# Power.net
KiCad netlist of a schematic drawn in Altium Designer
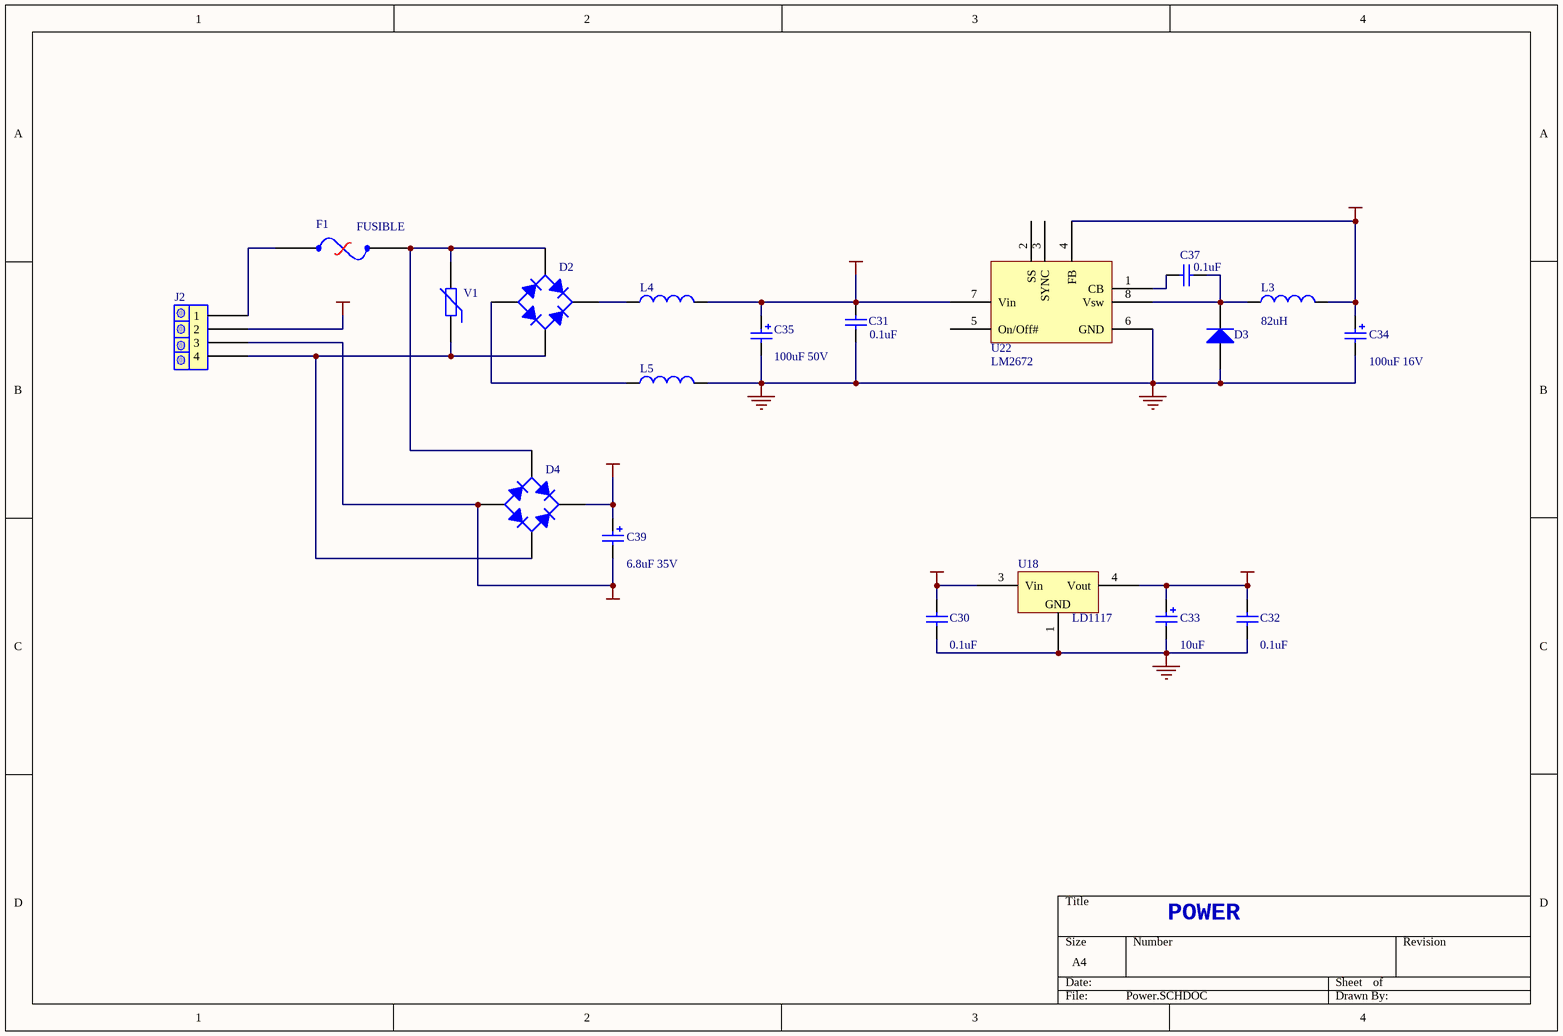
[diagram p0: Power.SCHDOC]

(export (version "E")
  (design (tool "Eeschema 10.0.6"))
  (components
    (comp (ref "C30")
      (value "0.1uF")
      (footprint "_0805")
      (description "Capacitor (Semiconductor SIM Model)")
      (fields (field (name "Comment") "Cap Semi") (field (name "PUBLISHER") "Altium Limited"))
      (libsource (lib "Miscellaneous Devices") (part "Cap Semi"))
    )
    (comp (ref "C31")
      (value "0.1uF")
      (footprint "_0805")
      (description "Capacitor (Semiconductor SIM Model)")
      (fields (field (name "Comment") "Cap Semi") (field (name "PUBLISHER") "Altium Limited"))
      (libsource (lib "Miscellaneous Devices") (part "Cap Semi"))
    )
    (comp (ref "C32")
      (value "0.1uF")
      (footprint "_0805")
      (description "Capacitor (Semiconductor SIM Model)")
      (fields (field (name "Comment") "Cap Semi") (field (name "PUBLISHER") "Altium Limited"))
      (libsource (lib "Miscellaneous Devices") (part "Cap Semi"))
    )
    (comp (ref "C33")
      (value "10uF")
      (footprint "TC3528-1411")
      (description "Polarized Capacitor (Surface Mount)")
      (fields (field (name "Comment") "Cap Pol3") (field (name "PUBLISHER") "Altium Limited"))
      (libsource (lib "Miscellaneous Devices") (part "Cap Pol3"))
    )
    (comp (ref "C34")
      (value "100uF 16V")
      (footprint "TC7360-2924")
      (description "Polarized Capacitor (Surface Mount)")
      (fields (field (name "Comment") "Cap Pol3") (field (name "PUBLISHER") "Altium Limited"))
      (libsource (lib "Miscellaneous Devices") (part "Cap Pol3"))
    )
    (comp (ref "C35")
      (value "100uF 50V")
      (footprint "CAPPR3.5-8X11.5")
      (description "Polarized Capacitor (Radial)")
      (fields (field (name "Comment") "Cap Pol1") (field (name "PUBLISHER") "Altium Limited"))
      (libsource (lib "Miscellaneous Devices") (part "Cap Pol1"))
    )
    (comp (ref "C37")
      (value "0.1uF")
      (footprint "_0805")
      (description "Capacitor (Semiconductor SIM Model)")
      (fields (field (name "Comment") "Cap Semi") (field (name "PUBLISHER") "Altium Limited"))
      (libsource (lib "Miscellaneous Devices") (part "Cap Semi"))
    )
    (comp (ref "C39")
      (value "6.8uF 35V")
      (footprint "TC6032-2412")
      (description "Polarized Capacitor (Surface Mount)")
      (fields (field (name "Comment") "Cap Pol3") (field (name "PUBLISHER") "Altium Limited"))
      (libsource (lib "Miscellaneous Devices") (part "Cap Pol3"))
    )
    (comp (ref "D2")
      (value "Bridge1")
      (footprint "BRIDGE_2A")
      (description "Full Wave Diode Bridge")
      (fields (field (name "PUBLISHER") "Altium Limited"))
      (libsource (lib "Miscellaneous Devices") (part "Bridge1"))
    )
    (comp (ref "D3")
      (value "Diode")
      (footprint "SMA")
      (description "Default Diode")
      (fields (field (name "PUBLISHER") "Altium Limited"))
      (libsource (lib "Miscellaneous Devices") (part "Diode"))
    )
    (comp (ref "D4")
      (value "Bridge1")
      (footprint "BRIDGE_2A")
      (description "Full Wave Diode Bridge")
      (fields (field (name "PUBLISHER") "Altium Limited"))
      (libsource (lib "Miscellaneous Devices") (part "Bridge1"))
    )
    (comp (ref "F1")
      (value "FUSIBLE")
      (footprint "FUSE")
      (description "Resetteable Fuse")
      (libsource (lib "Vending") (part "FUSIBLE"))
    )
    (comp (ref "J2")
      (value "BORNERA_X4")
      (footprint "BORNERA_X4")
      (libsource (lib "Custom") (part "BORNERA_X4"))
    )
    (comp (ref "L3")
      (value "82uH")
      (footprint "POWER_IND")
      (description "Inductor")
      (fields (field (name "PUBLISHER") "Altium Limited"))
      (libsource (lib "Miscellaneous Devices") (part "Inductor"))
    )
    (comp (ref "L4")
      (value "Inductor")
      (footprint "CR3225-1210")
      (fields (field (name "PUBLISHER") "Altium Limited"))
      (libsource (lib "Miscellaneous Devices") (part "Inductor"))
    )
    (comp (ref "L5")
      (value "Inductor")
      (footprint "CR3225-1210")
      (fields (field (name "PUBLISHER") "Altium Limited"))
      (libsource (lib "Miscellaneous Devices") (part "Inductor"))
    )
    (comp (ref "U18")
      (value "LD1117")
      (footprint "SIP-G3/D11.3")
      (description "SMD DPAK Voltage Regulator")
      (libsource (lib "Custom") (part "VREG_3V3_DPAK"))
    )
    (comp (ref "U22")
      (value "LM2672")
      (footprint "SO-G8/D5")
      (description "Simple switcher voltage regulator 1A")
      (libsource (lib "Custom") (part "LM2672"))
    )
    (comp (ref "V1")
      (value "Res Varistor")
      (footprint "CR3216-1206")
      (description "Varistor (Voltage-Sensitive Resistor)")
      (fields (field (name "PUBLISHER") "Altium Limited"))
      (libsource (lib "Miscellaneous Devices") (part "Res Varistor"))
    )
  )
  (nets
    (net (code "1") (name "GND") (class "Default")
      (node (ref "C30") (pin "1") (pinfunction "1_1") (pintype "passive"))
      (node (ref "C31") (pin "1") (pinfunction "1_1") (pintype "passive"))
      (node (ref "C32") (pin "1") (pinfunction "1_1") (pintype "passive"))
      (node (ref "C33") (pin "2") (pinfunction "2_2") (pintype "passive"))
      (node (ref "C34") (pin "2") (pinfunction "2_2") (pintype "passive"))
      (node (ref "C35") (pin "2") (pinfunction "2_2") (pintype "passive"))
      (node (ref "D3") (pin "1") (pinfunction "A_1") (pintype "passive"))
      (node (ref "L5") (pin "2") (pinfunction "2_2") (pintype "passive"))
      (node (ref "U18") (pin "1") (pinfunction "GND_1") (pintype "passive"))
      (node (ref "U22") (pin "6") (pinfunction "GND_6") (pintype "passive"))
    )
    (net (code "2") (name "GND_PWR") (class "Default")
      (node (ref "C39") (pin "2") (pinfunction "2_2") (pintype "passive"))
      (node (ref "D4") (pin "1") (pinfunction "A_1") (pintype "passive"))
      (node (ref "J2") (pin "3") (pinfunction "3_3") (pintype "passive"))
    )
    (net (code "3") (name "Net-(D2-A)") (class "Default")
      (node (ref "D2") (pin "1") (pinfunction "A_1") (pintype "passive"))
      (node (ref "L5") (pin "1") (pinfunction "1_1") (pintype "passive"))
    )
    (net (code "4") (name "Net-(D2-C-Pad2)") (class "Default")
      (node (ref "D2") (pin "2") (pinfunction "C_2") (pintype "passive"))
      (node (ref "D4") (pin "2") (pinfunction "C_2") (pintype "passive"))
      (node (ref "F1") (pin "2") (pinfunction "2_2") (pintype "passive"))
      (node (ref "V1") (pin "2") (pinfunction "2_2") (pintype "passive"))
    )
    (net (code "5") (name "Net-(D2-C-Pad4)") (class "Default")
      (node (ref "D2") (pin "4") (pinfunction "C_4") (pintype "passive"))
      (node (ref "D4") (pin "4") (pinfunction "C_4") (pintype "passive"))
      (node (ref "J2") (pin "4") (pinfunction "4_4") (pintype "passive"))
      (node (ref "V1") (pin "1") (pinfunction "1_1") (pintype "passive"))
    )
    (net (code "6") (name "Net-(D2-K)") (class "Default")
      (node (ref "D2") (pin "3") (pinfunction "K_3") (pintype "passive"))
      (node (ref "L4") (pin "1") (pinfunction "1_1") (pintype "passive"))
    )
    (net (code "7") (name "Net-(D3-K)") (class "Default")
      (node (ref "C37") (pin "1") (pinfunction "1_1") (pintype "passive"))
      (node (ref "D3") (pin "2") (pinfunction "K_2") (pintype "passive"))
      (node (ref "L3") (pin "1") (pinfunction "1_1") (pintype "passive"))
      (node (ref "U22") (pin "8") (pinfunction "Vsw_8") (pintype "passive"))
    )
    (net (code "8") (name "Net-(F1-Pad1)") (class "Default")
      (node (ref "F1") (pin "1") (pinfunction "1_1") (pintype "passive"))
      (node (ref "J2") (pin "1") (pinfunction "1_1") (pintype "passive"))
    )
    (net (code "9") (name "Net-(U22-CB)") (class "Default")
      (node (ref "C37") (pin "2") (pinfunction "2_2") (pintype "passive"))
      (node (ref "U22") (pin "1") (pinfunction "CB_1") (pintype "passive"))
    )
    (net (code "10") (name "VCC_3V") (class "Default")
      (node (ref "C32") (pin "2") (pinfunction "2_2") (pintype "passive"))
      (node (ref "C33") (pin "1") (pinfunction "1_1") (pintype "passive"))
      (node (ref "U18") (pin "4") (pinfunction "Vout_4") (pintype "passive"))
    )
    (net (code "11") (name "VCC_5V") (class "Default")
      (node (ref "C30") (pin "2") (pinfunction "2_2") (pintype "passive"))
      (node (ref "C34") (pin "1") (pinfunction "1_1") (pintype "passive"))
      (node (ref "L3") (pin "2") (pinfunction "2_2") (pintype "passive"))
      (node (ref "U18") (pin "3") (pinfunction "Vin_3") (pintype "power_in"))
      (node (ref "U22") (pin "4") (pinfunction "FB_4") (pintype "passive"))
    )
    (net (code "12") (name "VCC_IN") (class "Default")
      (node (ref "C31") (pin "2") (pinfunction "2_2") (pintype "passive"))
      (node (ref "C35") (pin "1") (pinfunction "1_1") (pintype "passive"))
      (node (ref "L4") (pin "2") (pinfunction "2_2") (pintype "passive"))
      (node (ref "U22") (pin "7") (pinfunction "Vin_7") (pintype "passive"))
    )
    (net (code "13") (name "VCC_PWR") (class "Default")
      (node (ref "C39") (pin "1") (pinfunction "1_1") (pintype "passive"))
      (node (ref "D4") (pin "3") (pinfunction "K_3") (pintype "passive"))
      (node (ref "J2") (pin "2") (pinfunction "2_2") (pintype "passive"))
    )
    (net (code "14") (name "unconnected-(U22-On{slash}Off#-Pad5)") (class "Default")
      (node (ref "U22") (pin "5") (pinfunction "On/Off#_5") (pintype "passive"))
    )
    (net (code "15") (name "unconnected-(U22-SS-Pad2)") (class "Default")
      (node (ref "U22") (pin "2") (pinfunction "SS_2") (pintype "passive"))
    )
    (net (code "16") (name "unconnected-(U22-SYNC-Pad3)") (class "Default")
      (node (ref "U22") (pin "3") (pinfunction "SYNC_3") (pintype "passive"))
    )
  )
)
